# Schematic.net
KiCad netlist of a schematic drawn in Altium Designer
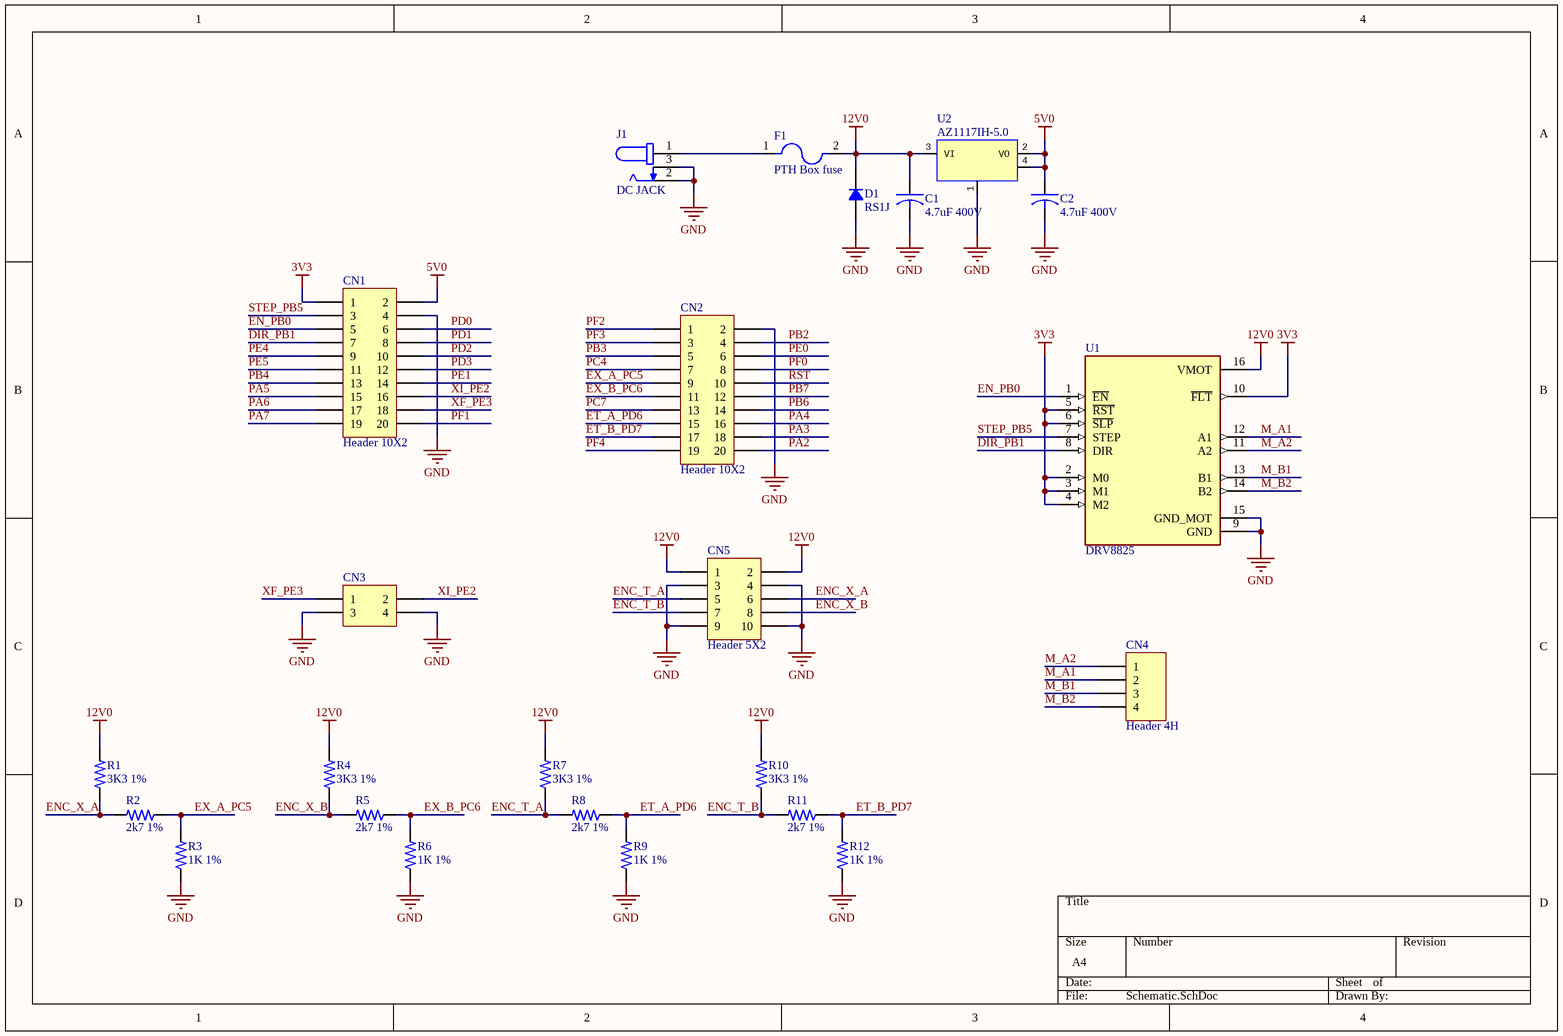
[diagram p0: Schematic.SchDoc]

(export (version "E")
  (design (tool "Eeschema 10.0.6"))
  (components
    (comp (ref "C1")
      (value "4.7uF 400V")
      (footprint "cap Aluminum 8x13mm Horizontal")
      (description "CAP ALUM 4.7UF 20% 400V RADIAL")
      (fields (field (name "MANUFACTURER") "ANY"))
      (libsource (lib "Capacitors") (part "4.7uF 400V PTH ALUM"))
    )
    (comp (ref "C2")
      (value "4.7uF 400V")
      (footprint "cap Aluminum 8x13mm Horizontal")
      (description "CAP ALUM 4.7UF 20% 400V RADIAL")
      (fields (field (name "MANUFACTURER") "ANY"))
      (libsource (lib "Capacitors") (part "4.7uF 400V PTH ALUM"))
    )
    (comp (ref "CN1")
      (value "Header 10X2")
      (footprint "Header 10x2")
      (description "Header, 10-Pin, Dual row")
      (fields (field (name "PUBLISHER") "Altium Limited"))
      (libsource (lib "Library") (part "Header 10X2"))
    )
    (comp (ref "CN2")
      (value "Header 10X2")
      (footprint "Header 10x2")
      (description "Header, 10-Pin, Dual row")
      (fields (field (name "PUBLISHER") "Altium Limited"))
      (libsource (lib "Library") (part "Header 10X2"))
    )
    (comp (ref "CN3")
      (value "Header 2X2 Right Angle")
      (footprint "Header 2x2 Right Angle")
      (description "Header, 2-Pin, Dual row, Right Angle")
      (fields (field (name "PUBLISHER") "Altium Limited"))
      (libsource (lib "Library") (part "Header 2X2 Right Angle"))
    )
    (comp (ref "CN4")
      (value "Header 4H")
      (footprint "HDR1X4H")
      (description "Header, 4-Pin, Right Angle")
      (fields (field (name "PUBLISHER") "Altium Limited"))
      (libsource (lib "Miscellaneous Connectors") (part "Header 4H"))
    )
    (comp (ref "CN5")
      (value "Header 5X2")
      (footprint "Header 5x2 Right Angle")
      (description "Header, 5-Pin, Dual row, Right Angle")
      (fields (field (name "PUBLISHER") "Altium Limited"))
      (libsource (lib "Library") (part "Header 5X2 Right Angle"))
    )
    (comp (ref "D1")
      (value "RS1J")
      (footprint "DO-214AC - ROUNDED")
      (description "DIODE GEN PURP 600V 1A DO214AC")
      (fields (field (name "MANUFACTURER") "ON Semiconductor") (field (name "Comment") "Fast Recovery"))
      (libsource (lib "Diodes") (part "RS1J"))
    )
    (comp (ref "F1")
      (value "PTH Box fuse")
      (footprint "FUSRR508W60L835T400H810")
      (description "Radial Box fuse")
      (libsource (lib "Bidirecional") (part "PTH Box fuse"))
    )
    (comp (ref "J1")
      (value "DC JACK")
      (footprint "DC JACK 2x6.5")
      (description "2.0 x 6.5 mm, 5.0 A, Horizontal, Through Hole, Dc Power Jack Connector")
      (fields (field (name "MF") "CUI Devices") (field (name "MP") "PJ-002AH"))
      (libsource (lib "Library") (part "DC JACK 2x6.5mm"))
    )
    (comp (ref "R1")
      (value "3K3 1%")
      (footprint "RES0603 - rounded")
      (description "RES SMD 3K3 1/16W 1% 0603")
      (fields (field (name "Comment") "3K3 1/16W 1% 0603"))
      (libsource (lib "Resistors") (part "3K3 1/16W 1% 0603"))
    )
    (comp (ref "R2")
      (value "2k7 1%")
      (footprint "RES0603 - rounded")
      (description "RES SMD 2k7 1/10W 1% 0603")
      (fields (field (name "Comment") "2k7 1/10W 1% 0603"))
      (libsource (lib "Resistors") (part "2k7 1/10W 1% 0603"))
    )
    (comp (ref "R3")
      (value "1K 1%")
      (footprint "RES0603 - rounded")
      (description "RES SMD 1K 1/10W 1% 0603")
      (fields (field (name "Comment") "1K 1/10W 1% 0603"))
      (libsource (lib "Resistors") (part "1K 1/10W 1% 0603"))
    )
    (comp (ref "R4")
      (value "3K3 1%")
      (footprint "RES0603 - rounded")
      (description "RES SMD 3K3 1/16W 1% 0603")
      (fields (field (name "Comment") "3K3 1/16W 1% 0603"))
      (libsource (lib "Resistors") (part "3K3 1/16W 1% 0603"))
    )
    (comp (ref "R5")
      (value "2k7 1%")
      (footprint "RES0603 - rounded")
      (description "RES SMD 2k7 1/10W 1% 0603")
      (fields (field (name "Comment") "2k7 1/10W 1% 0603"))
      (libsource (lib "Resistors") (part "2k7 1/10W 1% 0603"))
    )
    (comp (ref "R6")
      (value "1K 1%")
      (footprint "RES0603 - rounded")
      (description "RES SMD 1K 1/10W 1% 0603")
      (fields (field (name "Comment") "1K 1/10W 1% 0603"))
      (libsource (lib "Resistors") (part "1K 1/10W 1% 0603"))
    )
    (comp (ref "R7")
      (value "3K3 1%")
      (footprint "RES0603 - rounded")
      (description "RES SMD 3K3 1/16W 1% 0603")
      (fields (field (name "Comment") "3K3 1/16W 1% 0603"))
      (libsource (lib "Resistors") (part "3K3 1/16W 1% 0603"))
    )
    (comp (ref "R8")
      (value "2k7 1%")
      (footprint "RES0603 - rounded")
      (description "RES SMD 2k7 1/10W 1% 0603")
      (fields (field (name "Comment") "2k7 1/10W 1% 0603"))
      (libsource (lib "Resistors") (part "2k7 1/10W 1% 0603"))
    )
    (comp (ref "R9")
      (value "1K 1%")
      (footprint "RES0603 - rounded")
      (description "RES SMD 1K 1/10W 1% 0603")
      (fields (field (name "Comment") "1K 1/10W 1% 0603"))
      (libsource (lib "Resistors") (part "1K 1/10W 1% 0603"))
    )
    (comp (ref "R10")
      (value "3K3 1%")
      (footprint "RES0603 - rounded")
      (description "RES SMD 3K3 1/16W 1% 0603")
      (fields (field (name "Comment") "3K3 1/16W 1% 0603"))
      (libsource (lib "Resistors") (part "3K3 1/16W 1% 0603"))
    )
    (comp (ref "R11")
      (value "2k7 1%")
      (footprint "RES0603 - rounded")
      (description "RES SMD 2k7 1/10W 1% 0603")
      (fields (field (name "Comment") "2k7 1/10W 1% 0603"))
      (libsource (lib "Resistors") (part "2k7 1/10W 1% 0603"))
    )
    (comp (ref "R12")
      (value "1K 1%")
      (footprint "RES0603 - rounded")
      (description "RES SMD 1K 1/10W 1% 0603")
      (fields (field (name "Comment") "1K 1/10W 1% 0603"))
      (libsource (lib "Resistors") (part "1K 1/10W 1% 0603"))
    )
    (comp (ref "U1")
      (value "DRV8825")
      (footprint "Library:IC_DRV8825_STEPPER_MOTOR_DRIVER_CARRIER")
      (description "Stepper motor controler; IC: DRV8825; 1.5A; Uin mot: 8.2Ã·45V")
      (fields (field (name "MP") "DRV8825_STEPPER_MOTOR_DRIVER_CARRIER"))
      (libsource (lib "Library") (part "DRV8825_STEPPER_MOTOR_DRIVER_CARRIER"))
    )
    (comp (ref "U2")
      (value "AZ1117IH-5.0")
      (footprint "SOT-223")
      (description "IC REG LINEAR 3.3V 1A SOT223")
      (fields
        (field (name "MANUFACTURER") "Diodes")
        (field (name "MANUFACTURER PART NUMBER") "AZ1117IH-3.3TRG1")
      )
      (libsource (lib "Linear") (part "AZ1117IH-3.3TRG1"))
    )
  )
  (nets
    (net (code "1") (name "/DIR_PB1") (class "Default")
      (node (ref "CN1") (pin "7") (pinfunction "7_7") (pintype "passive"))
      (node (ref "U1") (pin "8") (pinfunction "DIR_8") (pintype "input"))
    )
    (net (code "2") (name "/ENC_T_A") (class "Default")
      (node (ref "CN5") (pin "5") (pinfunction "5_5") (pintype "passive"))
      (node (ref "R7") (pin "1") (pinfunction "1_1") (pintype "passive"))
      (node (ref "R8") (pin "2") (pinfunction "2_2") (pintype "passive"))
    )
    (net (code "3") (name "/ENC_T_B") (class "Default")
      (node (ref "CN5") (pin "7") (pinfunction "7_7") (pintype "passive"))
      (node (ref "R10") (pin "1") (pinfunction "1_1") (pintype "passive"))
      (node (ref "R11") (pin "2") (pinfunction "2_2") (pintype "passive"))
    )
    (net (code "4") (name "/ENC_X_A") (class "Default")
      (node (ref "CN5") (pin "6") (pinfunction "6_6") (pintype "passive"))
      (node (ref "R1") (pin "1") (pinfunction "1_1") (pintype "passive"))
      (node (ref "R2") (pin "2") (pinfunction "2_2") (pintype "passive"))
    )
    (net (code "5") (name "/ENC_X_B") (class "Default")
      (node (ref "CN5") (pin "8") (pinfunction "8_8") (pintype "passive"))
      (node (ref "R4") (pin "1") (pinfunction "1_1") (pintype "passive"))
      (node (ref "R5") (pin "2") (pinfunction "2_2") (pintype "passive"))
    )
    (net (code "6") (name "/EN_PB0") (class "Default")
      (node (ref "CN1") (pin "5") (pinfunction "5_5") (pintype "passive"))
      (node (ref "U1") (pin "1") (pinfunction "~{EN}_1") (pintype "input"))
    )
    (net (code "7") (name "/ET_A_PD6") (class "Default")
      (node (ref "CN2") (pin "15") (pinfunction "15_15") (pintype "passive"))
      (node (ref "R8") (pin "1") (pinfunction "1_1") (pintype "passive"))
      (node (ref "R9") (pin "2") (pinfunction "2_2") (pintype "passive"))
    )
    (net (code "8") (name "/ET_B_PD7") (class "Default")
      (node (ref "CN2") (pin "17") (pinfunction "17_17") (pintype "passive"))
      (node (ref "R11") (pin "1") (pinfunction "1_1") (pintype "passive"))
      (node (ref "R12") (pin "2") (pinfunction "2_2") (pintype "passive"))
    )
    (net (code "9") (name "/EX_A_PC5") (class "Default")
      (node (ref "CN2") (pin "9") (pinfunction "9_9") (pintype "passive"))
      (node (ref "R2") (pin "1") (pinfunction "1_1") (pintype "passive"))
      (node (ref "R3") (pin "2") (pinfunction "2_2") (pintype "passive"))
    )
    (net (code "10") (name "/EX_B_PC6") (class "Default")
      (node (ref "CN2") (pin "11") (pinfunction "11_11") (pintype "passive"))
      (node (ref "R5") (pin "1") (pinfunction "1_1") (pintype "passive"))
      (node (ref "R6") (pin "2") (pinfunction "2_2") (pintype "passive"))
    )
    (net (code "11") (name "/M_A1") (class "Default")
      (node (ref "CN4") (pin "2") (pinfunction "2_2") (pintype "passive"))
      (node (ref "U1") (pin "12") (pinfunction "A1_12") (pintype "output"))
    )
    (net (code "12") (name "/M_A2") (class "Default")
      (node (ref "CN4") (pin "1") (pinfunction "1_1") (pintype "passive"))
      (node (ref "U1") (pin "11") (pinfunction "A2_11") (pintype "output"))
    )
    (net (code "13") (name "/M_B1") (class "Default")
      (node (ref "CN4") (pin "3") (pinfunction "3_3") (pintype "passive"))
      (node (ref "U1") (pin "13") (pinfunction "B1_13") (pintype "output"))
    )
    (net (code "14") (name "/M_B2") (class "Default")
      (node (ref "CN4") (pin "4") (pinfunction "4_4") (pintype "passive"))
      (node (ref "U1") (pin "14") (pinfunction "B2_14") (pintype "output"))
    )
    (net (code "15") (name "/PA2") (class "Default")
      (node (ref "CN2") (pin "20") (pinfunction "20_20") (pintype "passive"))
    )
    (net (code "16") (name "/PA3") (class "Default")
      (node (ref "CN2") (pin "18") (pinfunction "18_18") (pintype "passive"))
    )
    (net (code "17") (name "/PA4") (class "Default")
      (node (ref "CN2") (pin "16") (pinfunction "16_16") (pintype "passive"))
    )
    (net (code "18") (name "/PA5") (class "Default")
      (node (ref "CN1") (pin "15") (pinfunction "15_15") (pintype "passive"))
    )
    (net (code "19") (name "/PA6") (class "Default")
      (node (ref "CN1") (pin "17") (pinfunction "17_17") (pintype "passive"))
    )
    (net (code "20") (name "/PA7") (class "Default")
      (node (ref "CN1") (pin "19") (pinfunction "19_19") (pintype "passive"))
    )
    (net (code "21") (name "/PB2") (class "Default")
      (node (ref "CN2") (pin "4") (pinfunction "4_4") (pintype "passive"))
    )
    (net (code "22") (name "/PB3") (class "Default")
      (node (ref "CN2") (pin "5") (pinfunction "5_5") (pintype "passive"))
    )
    (net (code "23") (name "/PB4") (class "Default")
      (node (ref "CN1") (pin "13") (pinfunction "13_13") (pintype "passive"))
    )
    (net (code "24") (name "/PB6") (class "Default")
      (node (ref "CN2") (pin "14") (pinfunction "14_14") (pintype "passive"))
    )
    (net (code "25") (name "/PB7") (class "Default")
      (node (ref "CN2") (pin "12") (pinfunction "12_12") (pintype "passive"))
    )
    (net (code "26") (name "/PC4") (class "Default")
      (node (ref "CN2") (pin "7") (pinfunction "7_7") (pintype "passive"))
    )
    (net (code "27") (name "/PC7") (class "Default")
      (node (ref "CN2") (pin "13") (pinfunction "13_13") (pintype "passive"))
    )
    (net (code "28") (name "/PD0") (class "Default")
      (node (ref "CN1") (pin "6") (pinfunction "6_6") (pintype "passive"))
    )
    (net (code "29") (name "/PD1") (class "Default")
      (node (ref "CN1") (pin "8") (pinfunction "8_8") (pintype "passive"))
    )
    (net (code "30") (name "/PD2") (class "Default")
      (node (ref "CN1") (pin "10") (pinfunction "10_10") (pintype "passive"))
    )
    (net (code "31") (name "/PD3") (class "Default")
      (node (ref "CN1") (pin "12") (pinfunction "12_12") (pintype "passive"))
    )
    (net (code "32") (name "/PE0") (class "Default")
      (node (ref "CN2") (pin "6") (pinfunction "6_6") (pintype "passive"))
    )
    (net (code "33") (name "/PE1") (class "Default")
      (node (ref "CN1") (pin "14") (pinfunction "14_14") (pintype "passive"))
    )
    (net (code "34") (name "/PE4") (class "Default")
      (node (ref "CN1") (pin "9") (pinfunction "9_9") (pintype "passive"))
    )
    (net (code "35") (name "/PE5") (class "Default")
      (node (ref "CN1") (pin "11") (pinfunction "11_11") (pintype "passive"))
    )
    (net (code "36") (name "/PF0") (class "Default")
      (node (ref "CN2") (pin "8") (pinfunction "8_8") (pintype "passive"))
    )
    (net (code "37") (name "/PF1") (class "Default")
      (node (ref "CN1") (pin "20") (pinfunction "20_20") (pintype "passive"))
    )
    (net (code "38") (name "/PF2") (class "Default")
      (node (ref "CN2") (pin "1") (pinfunction "1_1") (pintype "passive"))
    )
    (net (code "39") (name "/PF3") (class "Default")
      (node (ref "CN2") (pin "3") (pinfunction "3_3") (pintype "passive"))
    )
    (net (code "40") (name "/PF4") (class "Default")
      (node (ref "CN2") (pin "19") (pinfunction "19_19") (pintype "passive"))
    )
    (net (code "41") (name "/RST") (class "Default")
      (node (ref "CN2") (pin "10") (pinfunction "10_10") (pintype "passive"))
    )
    (net (code "42") (name "/STEP_PB5") (class "Default")
      (node (ref "CN1") (pin "3") (pinfunction "3_3") (pintype "passive"))
      (node (ref "U1") (pin "7") (pinfunction "STEP_7") (pintype "input"))
    )
    (net (code "43") (name "/XF_PE3") (class "Default")
      (node (ref "CN1") (pin "18") (pinfunction "18_18") (pintype "passive"))
      (node (ref "CN3") (pin "1") (pinfunction "1_1") (pintype "passive"))
    )
    (net (code "44") (name "/XI_PE2") (class "Default")
      (node (ref "CN1") (pin "16") (pinfunction "16_16") (pintype "passive"))
      (node (ref "CN3") (pin "2") (pinfunction "2_2") (pintype "passive"))
    )
    (net (code "45") (name "3V3") (class "Default")
      (node (ref "CN1") (pin "1") (pinfunction "1_1") (pintype "passive"))
      (node (ref "U1") (pin "10") (pinfunction "~{FLT}_10") (pintype "output"))
      (node (ref "U1") (pin "2") (pinfunction "M0_2") (pintype "input"))
      (node (ref "U1") (pin "3") (pinfunction "M1_3") (pintype "input"))
      (node (ref "U1") (pin "4") (pinfunction "M2_4") (pintype "input"))
      (node (ref "U1") (pin "5") (pinfunction "~{RST}_5") (pintype "input"))
      (node (ref "U1") (pin "6") (pinfunction "~{SLP}_6") (pintype "input"))
    )
    (net (code "46") (name "5V0") (class "Default")
      (node (ref "C2") (pin "1") (pinfunction "1_1") (pintype "passive"))
      (node (ref "CN1") (pin "2") (pinfunction "2_2") (pintype "passive"))
      (node (ref "U2") (pin "2") (pinfunction "VO_2") (pintype "passive"))
      (node (ref "U2") (pin "4") (pinfunction "VO_4") (pintype "passive"))
    )
    (net (code "47") (name "12V0") (class "Default")
      (node (ref "C1") (pin "1") (pinfunction "1_1") (pintype "passive"))
      (node (ref "CN5") (pin "1") (pinfunction "1_1") (pintype "passive"))
      (node (ref "CN5") (pin "2") (pinfunction "2_2") (pintype "passive"))
      (node (ref "D1") (pin "K") (pinfunction "K_K") (pintype "passive"))
      (node (ref "F1") (pin "2") (pinfunction "2_2") (pintype "passive"))
      (node (ref "R1") (pin "2") (pinfunction "2_2") (pintype "passive"))
      (node (ref "R10") (pin "2") (pinfunction "2_2") (pintype "passive"))
      (node (ref "R4") (pin "2") (pinfunction "2_2") (pintype "passive"))
      (node (ref "R7") (pin "2") (pinfunction "2_2") (pintype "passive"))
      (node (ref "U1") (pin "16") (pinfunction "VMOT_16") (pintype "power_in"))
      (node (ref "U2") (pin "3") (pinfunction "VI_3") (pintype "passive"))
    )
    (net (code "48") (name "GND") (class "Default")
      (node (ref "C1") (pin "2") (pinfunction "2_2") (pintype "passive"))
      (node (ref "C2") (pin "2") (pinfunction "2_2") (pintype "passive"))
      (node (ref "CN1") (pin "4") (pinfunction "4_4") (pintype "passive"))
      (node (ref "CN2") (pin "2") (pinfunction "2_2") (pintype "passive"))
      (node (ref "CN3") (pin "3") (pinfunction "3_3") (pintype "passive"))
      (node (ref "CN3") (pin "4") (pinfunction "4_4") (pintype "passive"))
      (node (ref "CN5") (pin "10") (pinfunction "10_10") (pintype "passive"))
      (node (ref "CN5") (pin "3") (pinfunction "3_3") (pintype "passive"))
      (node (ref "CN5") (pin "4") (pinfunction "4_4") (pintype "passive"))
      (node (ref "CN5") (pin "9") (pinfunction "9_9") (pintype "passive"))
      (node (ref "D1") (pin "A") (pinfunction "A_A") (pintype "passive"))
      (node (ref "J1") (pin "2") (pinfunction "2_2") (pintype "passive"))
      (node (ref "J1") (pin "3") (pinfunction "3_3") (pintype "passive"))
      (node (ref "R12") (pin "1") (pinfunction "1_1") (pintype "passive"))
      (node (ref "R3") (pin "1") (pinfunction "1_1") (pintype "passive"))
      (node (ref "R6") (pin "1") (pinfunction "1_1") (pintype "passive"))
      (node (ref "R9") (pin "1") (pinfunction "1_1") (pintype "passive"))
      (node (ref "U1") (pin "15") (pinfunction "GND_MOT_15") (pintype "power_in"))
      (node (ref "U1") (pin "9") (pinfunction "GND_9") (pintype "power_in"))
      (node (ref "U2") (pin "1") (pinfunction "GND_1") (pintype "passive"))
    )
    (net (code "49") (name "Net-(F1-Pad1)") (class "Default")
      (node (ref "F1") (pin "1") (pinfunction "1_1") (pintype "passive"))
      (node (ref "J1") (pin "1") (pinfunction "1_1") (pintype "passive"))
    )
  )
)
